# Sheet5.net
KiCad netlist of a schematic drawn in Altium Designer
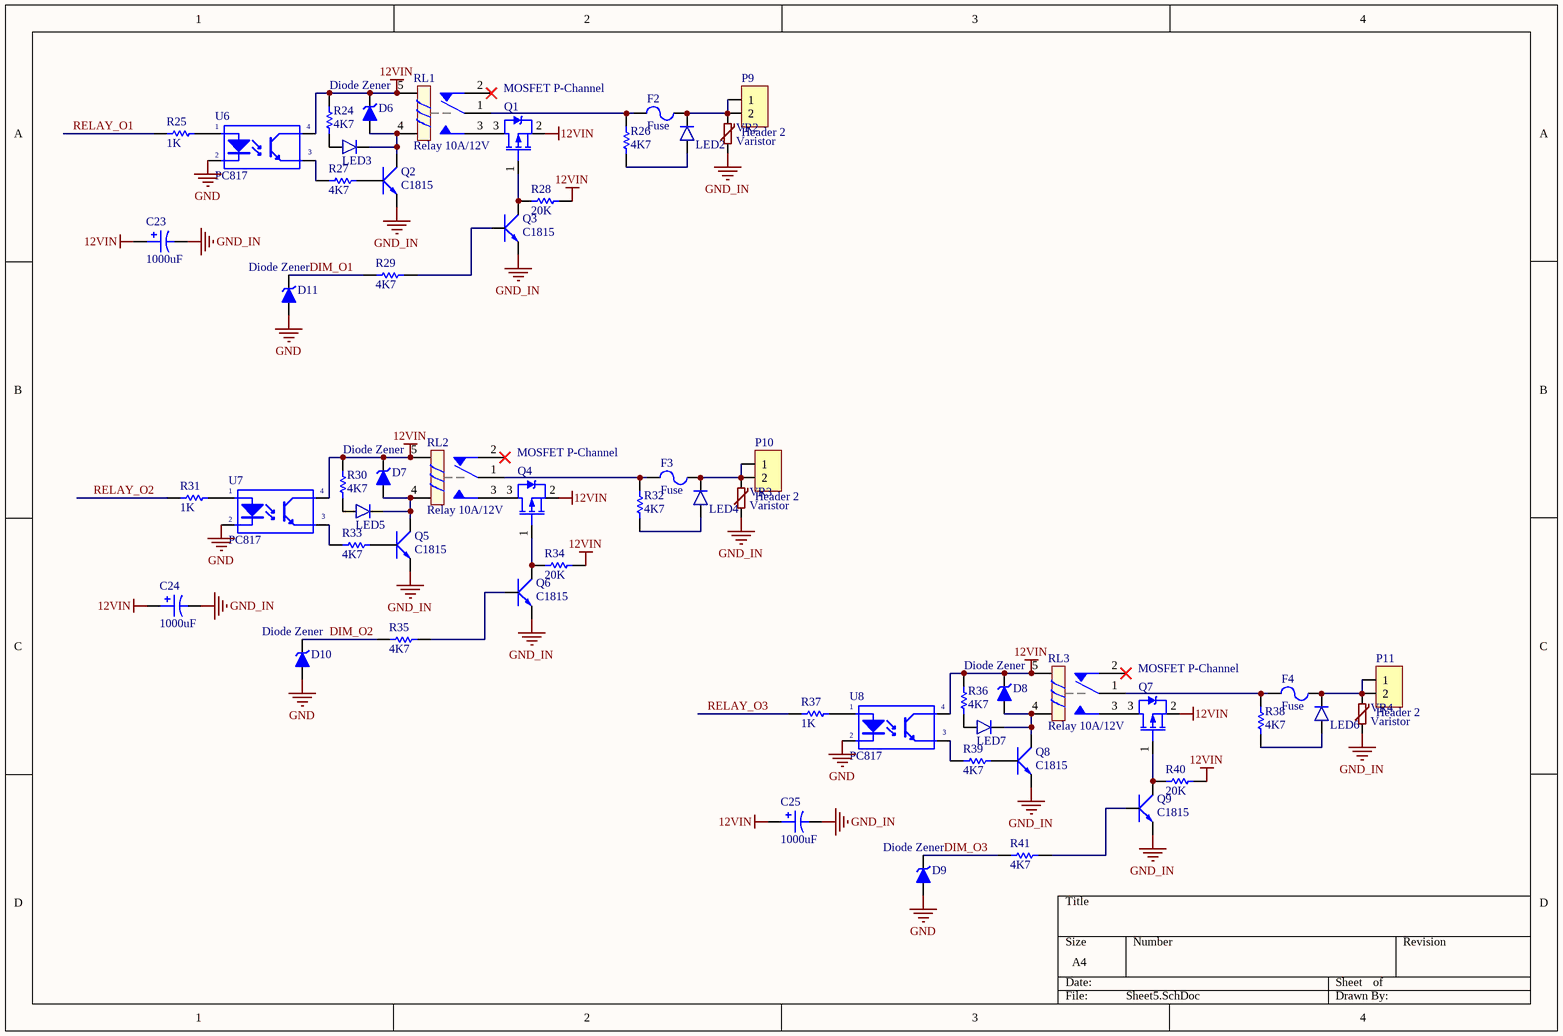
[diagram p0: Sheet5.SchDoc]

(export (version "E")
  (design (tool "Eeschema 10.0.6"))
  (components
    (comp (ref "C23")
      (value "1000uF")
      (footprint "RADIAL E")
      (description "Polarized Capacitor")
      (fields (field (name "Comment") "Cap Pol") (field (name "PUBLISHER") "Altium Limited"))
      (libsource (lib "phong") (part "Cap Pol"))
    )
    (comp (ref "C24")
      (value "1000uF")
      (footprint "RADIAL E")
      (description "Polarized Capacitor")
      (fields (field (name "Comment") "Cap Pol") (field (name "PUBLISHER") "Altium Limited"))
      (libsource (lib "phong") (part "Cap Pol"))
    )
    (comp (ref "C25")
      (value "1000uF")
      (footprint "RADIAL E")
      (description "Polarized Capacitor")
      (fields (field (name "Comment") "Cap Pol") (field (name "PUBLISHER") "Altium Limited"))
      (libsource (lib "phong") (part "Cap Pol"))
    )
    (comp (ref "D6")
      (value "Diode Zener")
      (footprint "SOD-80")
      (description "Zener Diode")
      (fields (field (name "PUBLISHER") "Altium Limited"))
      (libsource (lib "BKIT4U_LIB") (part "Diode Zener"))
    )
    (comp (ref "D7")
      (value "Diode Zener")
      (footprint "SOD-80")
      (description "Zener Diode")
      (fields (field (name "PUBLISHER") "Altium Limited"))
      (libsource (lib "BKIT4U_LIB") (part "Diode Zener"))
    )
    (comp (ref "D8")
      (value "Diode Zener")
      (footprint "SOD-80")
      (description "Zener Diode")
      (fields (field (name "PUBLISHER") "Altium Limited"))
      (libsource (lib "BKIT4U_LIB") (part "Diode Zener"))
    )
    (comp (ref "D9")
      (value "Diode Zener")
      (footprint "SOD-80")
      (description "Zener Diode")
      (fields (field (name "PUBLISHER") "Altium Limited"))
      (libsource (lib "BKIT4U_LIB") (part "Diode Zener"))
    )
    (comp (ref "D10")
      (value "Diode Zener")
      (footprint "SOD-80")
      (description "Zener Diode")
      (fields (field (name "PUBLISHER") "Altium Limited"))
      (libsource (lib "BKIT4U_LIB") (part "Diode Zener"))
    )
    (comp (ref "D11")
      (value "Diode Zener")
      (footprint "SOD-80")
      (description "Zener Diode")
      (fields (field (name "PUBLISHER") "Altium Limited"))
      (libsource (lib "BKIT4U_LIB") (part "Diode Zener"))
    )
    (comp (ref "F2")
      (value "Fuse")
      (footprint "DCAR Fuse holder")
      (libsource (lib "BKIT4U_LIB") (part "Fuse"))
    )
    (comp (ref "F3")
      (value "Fuse")
      (footprint "DCAR Fuse holder")
      (libsource (lib "BKIT4U_LIB") (part "Fuse"))
    )
    (comp (ref "F4")
      (value "Fuse")
      (footprint "DCAR Fuse holder")
      (libsource (lib "BKIT4U_LIB") (part "Fuse"))
    )
    (comp (ref "LED2")
      (value "Led")
      (footprint "Led SMD 0805")
      (description "Typical LED")
      (libsource (lib "BKIT4U_LIB") (part "Led"))
    )
    (comp (ref "LED3")
      (value "Led")
      (footprint "Led SMD 0805")
      (description "Typical LED")
      (libsource (lib "BKIT4U_LIB") (part "Led"))
    )
    (comp (ref "LED4")
      (value "Led")
      (footprint "Led SMD 0805")
      (description "Typical LED")
      (libsource (lib "BKIT4U_LIB") (part "Led"))
    )
    (comp (ref "LED5")
      (value "Led")
      (footprint "Led SMD 0805")
      (description "Typical LED")
      (libsource (lib "BKIT4U_LIB") (part "Led"))
    )
    (comp (ref "LED6")
      (value "Led")
      (footprint "Led SMD 0805")
      (description "Typical LED")
      (libsource (lib "BKIT4U_LIB") (part "Led"))
    )
    (comp (ref "LED7")
      (value "Led")
      (footprint "Led SMD 0805")
      (description "Typical LED")
      (libsource (lib "BKIT4U_LIB") (part "Led"))
    )
    (comp (ref "P9")
      (value "Header 2")
      (footprint "HDR Domino 2")
      (description "Header, 2-Pin")
      (fields (field (name "PUBLISHER") "Altium Limited"))
      (libsource (lib "BKIT4U_LIB") (part "Header 2"))
    )
    (comp (ref "P10")
      (value "Header 2")
      (footprint "HDR Domino 2")
      (description "Header, 2-Pin")
      (fields (field (name "PUBLISHER") "Altium Limited"))
      (libsource (lib "BKIT4U_LIB") (part "Header 2"))
    )
    (comp (ref "P11")
      (value "Header 2")
      (footprint "HDR Domino 2")
      (description "Header, 2-Pin")
      (fields (field (name "PUBLISHER") "Altium Limited"))
      (libsource (lib "BKIT4U_LIB") (part "Header 2"))
    )
    (comp (ref "Q1")
      (value "MOSFET P-Channel")
      (footprint "TO-252 (DPAK)")
      (libsource (lib "BKIT4U_LIB") (part "MOSFET P-Channel"))
    )
    (comp (ref "Q2")
      (value "C1815")
      (footprint "SOT23B")
      (description "NPN 600mW, ECB")
      (libsource (lib "syhaunguyen") (part "C1815"))
    )
    (comp (ref "Q3")
      (value "C1815")
      (footprint "SOT23B")
      (description "NPN 600mW, ECB")
      (libsource (lib "syhaunguyen") (part "C1815"))
    )
    (comp (ref "Q4")
      (value "MOSFET P-Channel")
      (footprint "TO-252 (DPAK)")
      (libsource (lib "BKIT4U_LIB") (part "MOSFET P-Channel"))
    )
    (comp (ref "Q5")
      (value "C1815")
      (footprint "SOT23B")
      (description "NPN 600mW, ECB")
      (libsource (lib "syhaunguyen") (part "C1815"))
    )
    (comp (ref "Q6")
      (value "C1815")
      (footprint "SOT23B")
      (description "NPN 600mW, ECB")
      (libsource (lib "syhaunguyen") (part "C1815"))
    )
    (comp (ref "Q7")
      (value "MOSFET P-Channel")
      (footprint "TO-252 (DPAK)")
      (libsource (lib "BKIT4U_LIB") (part "MOSFET P-Channel"))
    )
    (comp (ref "Q8")
      (value "C1815")
      (footprint "SOT23B")
      (description "NPN 600mW, ECB")
      (libsource (lib "syhaunguyen") (part "C1815"))
    )
    (comp (ref "Q9")
      (value "C1815")
      (footprint "SOT23B")
      (description "NPN 600mW, ECB")
      (libsource (lib "syhaunguyen") (part "C1815"))
    )
    (comp (ref "R24")
      (value "4K7")
      (footprint "R 0805 (2012)")
      (description "Resistor")
      (fields (field (name "PUBLISHER") "Altium Limited"))
      (libsource (lib "BKIT4U_LIB") (part "Resistor"))
    )
    (comp (ref "R25")
      (value "1K")
      (footprint "R 0805 (2012)")
      (description "Resistor")
      (fields (field (name "PUBLISHER") "Altium Limited"))
      (libsource (lib "BKIT4U_LIB") (part "Resistor"))
    )
    (comp (ref "R26")
      (value "4K7")
      (footprint "R 0805 (2012)")
      (description "Resistor")
      (fields (field (name "PUBLISHER") "Altium Limited"))
      (libsource (lib "BKIT4U_LIB") (part "Resistor"))
    )
    (comp (ref "R27")
      (value "4K7")
      (footprint "R 0805 (2012)")
      (description "Resistor")
      (fields (field (name "PUBLISHER") "Altium Limited"))
      (libsource (lib "BKIT4U_LIB") (part "Resistor"))
    )
    (comp (ref "R28")
      (value "20K")
      (footprint "R 0805 (2012)")
      (description "Resistor")
      (fields (field (name "PUBLISHER") "Altium Limited"))
      (libsource (lib "BKIT4U_LIB") (part "Resistor"))
    )
    (comp (ref "R29")
      (value "4K7")
      (footprint "R 0805 (2012)")
      (description "Resistor")
      (fields (field (name "PUBLISHER") "Altium Limited"))
      (libsource (lib "BKIT4U_LIB") (part "Resistor"))
    )
    (comp (ref "R30")
      (value "4K7")
      (footprint "R 0805 (2012)")
      (description "Resistor")
      (fields (field (name "PUBLISHER") "Altium Limited"))
      (libsource (lib "BKIT4U_LIB") (part "Resistor"))
    )
    (comp (ref "R31")
      (value "1K")
      (footprint "R 0805 (2012)")
      (description "Resistor")
      (fields (field (name "PUBLISHER") "Altium Limited"))
      (libsource (lib "BKIT4U_LIB") (part "Resistor"))
    )
    (comp (ref "R32")
      (value "4K7")
      (footprint "R 0805 (2012)")
      (description "Resistor")
      (fields (field (name "PUBLISHER") "Altium Limited"))
      (libsource (lib "BKIT4U_LIB") (part "Resistor"))
    )
    (comp (ref "R33")
      (value "4K7")
      (footprint "R 0805 (2012)")
      (description "Resistor")
      (fields (field (name "PUBLISHER") "Altium Limited"))
      (libsource (lib "BKIT4U_LIB") (part "Resistor"))
    )
    (comp (ref "R34")
      (value "20K")
      (footprint "R 0805 (2012)")
      (description "Resistor")
      (fields (field (name "PUBLISHER") "Altium Limited"))
      (libsource (lib "BKIT4U_LIB") (part "Resistor"))
    )
    (comp (ref "R35")
      (value "4K7")
      (footprint "R 0805 (2012)")
      (description "Resistor")
      (fields (field (name "PUBLISHER") "Altium Limited"))
      (libsource (lib "BKIT4U_LIB") (part "Resistor"))
    )
    (comp (ref "R36")
      (value "4K7")
      (footprint "R 0805 (2012)")
      (description "Resistor")
      (fields (field (name "PUBLISHER") "Altium Limited"))
      (libsource (lib "BKIT4U_LIB") (part "Resistor"))
    )
    (comp (ref "R37")
      (value "1K")
      (footprint "R 0805 (2012)")
      (description "Resistor")
      (fields (field (name "PUBLISHER") "Altium Limited"))
      (libsource (lib "BKIT4U_LIB") (part "Resistor"))
    )
    (comp (ref "R38")
      (value "4K7")
      (footprint "R 0805 (2012)")
      (description "Resistor")
      (fields (field (name "PUBLISHER") "Altium Limited"))
      (libsource (lib "BKIT4U_LIB") (part "Resistor"))
    )
    (comp (ref "R39")
      (value "4K7")
      (footprint "R 0805 (2012)")
      (description "Resistor")
      (fields (field (name "PUBLISHER") "Altium Limited"))
      (libsource (lib "BKIT4U_LIB") (part "Resistor"))
    )
    (comp (ref "R40")
      (value "20K")
      (footprint "R 0805 (2012)")
      (description "Resistor")
      (fields (field (name "PUBLISHER") "Altium Limited"))
      (libsource (lib "BKIT4U_LIB") (part "Resistor"))
    )
    (comp (ref "R41")
      (value "4K7")
      (footprint "R 0805 (2012)")
      (description "Resistor")
      (fields (field (name "PUBLISHER") "Altium Limited"))
      (libsource (lib "BKIT4U_LIB") (part "Resistor"))
    )
    (comp (ref "RL1")
      (value "Relay 10A/12V")
      (footprint "RL_SPDT_10A")
      (description "Relay SPDT,10A - 12VDC 5 Pin")
      (libsource (lib "BKIT4U_LIB") (part "Relay 1"))
    )
    (comp (ref "RL2")
      (value "Relay 10A/12V")
      (footprint "RL_SPDT_10A")
      (description "Relay SPDT,10A - 12VDC 5 Pin")
      (libsource (lib "BKIT4U_LIB") (part "Relay 1"))
    )
    (comp (ref "RL3")
      (value "Relay 10A/12V")
      (footprint "RL_SPDT_10A")
      (description "Relay SPDT,10A - 12VDC 5 Pin")
      (libsource (lib "BKIT4U_LIB") (part "Relay 1"))
    )
    (comp (ref "U6")
      (value "PC817")
      (footprint "SOP4 - PC817")
      (description "Single Opto")
      (libsource (lib "syhaunguyen") (part "PC817"))
    )
    (comp (ref "U7")
      (value "PC817")
      (footprint "SOP4 - PC817")
      (description "Single Opto")
      (libsource (lib "syhaunguyen") (part "PC817"))
    )
    (comp (ref "U8")
      (value "PC817")
      (footprint "SOP4 - PC817")
      (description "Single Opto")
      (libsource (lib "syhaunguyen") (part "PC817"))
    )
    (comp (ref "VR2")
      (value "Varistor")
      (footprint "VARISTOR DISC 5MM/7MM")
      (libsource (lib "chipfc_altium_libs") (part "Varistor"))
    )
    (comp (ref "VR3")
      (value "Varistor")
      (footprint "VARISTOR DISC 5MM/7MM")
      (libsource (lib "chipfc_altium_libs") (part "Varistor"))
    )
    (comp (ref "VR4")
      (value "Varistor")
      (footprint "VARISTOR DISC 5MM/7MM")
      (libsource (lib "chipfc_altium_libs") (part "Varistor"))
    )
  )
  (nets
    (net (code "1") (name "/DIM_O1") (class "Default")
      (node (ref "D11") (pin "2") (pinfunction "K_2") (pintype "passive"))
      (node (ref "R29") (pin "1") (pinfunction "1_1") (pintype "passive"))
    )
    (net (code "2") (name "/DIM_O2") (class "Default")
      (node (ref "D10") (pin "2") (pinfunction "K_2") (pintype "passive"))
      (node (ref "R35") (pin "1") (pinfunction "1_1") (pintype "passive"))
    )
    (net (code "3") (name "/DIM_O3") (class "Default")
      (node (ref "D9") (pin "2") (pinfunction "K_2") (pintype "passive"))
      (node (ref "R41") (pin "1") (pinfunction "1_1") (pintype "passive"))
    )
    (net (code "4") (name "/RELAY_O1") (class "Default")
      (node (ref "R25") (pin "2") (pinfunction "2_2") (pintype "passive"))
    )
    (net (code "5") (name "/RELAY_O2") (class "Default")
      (node (ref "R31") (pin "2") (pinfunction "2_2") (pintype "passive"))
    )
    (net (code "6") (name "/RELAY_O3") (class "Default")
      (node (ref "R37") (pin "2") (pinfunction "2_2") (pintype "passive"))
    )
    (net (code "7") (name "12VIN") (class "Default")
      (node (ref "C23") (pin "1") (pinfunction "1_1") (pintype "passive"))
      (node (ref "C24") (pin "1") (pinfunction "1_1") (pintype "passive"))
      (node (ref "C25") (pin "1") (pinfunction "1_1") (pintype "passive"))
      (node (ref "D6") (pin "2") (pinfunction "K_2") (pintype "passive"))
      (node (ref "D7") (pin "2") (pinfunction "K_2") (pintype "passive"))
      (node (ref "D8") (pin "2") (pinfunction "K_2") (pintype "passive"))
      (node (ref "Q1") (pin "2") (pinfunction "S_2") (pintype "passive"))
      (node (ref "Q4") (pin "2") (pinfunction "S_2") (pintype "passive"))
      (node (ref "Q7") (pin "2") (pinfunction "S_2") (pintype "passive"))
      (node (ref "R24") (pin "2") (pinfunction "2_2") (pintype "passive"))
      (node (ref "R28") (pin "2") (pinfunction "2_2") (pintype "passive"))
      (node (ref "R30") (pin "2") (pinfunction "2_2") (pintype "passive"))
      (node (ref "R34") (pin "2") (pinfunction "2_2") (pintype "passive"))
      (node (ref "R36") (pin "2") (pinfunction "2_2") (pintype "passive"))
      (node (ref "R40") (pin "2") (pinfunction "2_2") (pintype "passive"))
      (node (ref "RL1") (pin "5") (pinfunction "5_5") (pintype "passive"))
      (node (ref "RL2") (pin "5") (pinfunction "5_5") (pintype "passive"))
      (node (ref "RL3") (pin "5") (pinfunction "5_5") (pintype "passive"))
      (node (ref "U6") (pin "4") (pinfunction "C_4") (pintype "passive"))
      (node (ref "U7") (pin "4") (pinfunction "C_4") (pintype "passive"))
      (node (ref "U8") (pin "4") (pinfunction "C_4") (pintype "passive"))
    )
    (net (code "8") (name "GND") (class "Default")
      (node (ref "D10") (pin "1") (pinfunction "A_1") (pintype "passive"))
      (node (ref "D11") (pin "1") (pinfunction "A_1") (pintype "passive"))
      (node (ref "D9") (pin "1") (pinfunction "A_1") (pintype "passive"))
      (node (ref "U6") (pin "2") (pinfunction "K_2") (pintype "passive"))
      (node (ref "U7") (pin "2") (pinfunction "K_2") (pintype "passive"))
      (node (ref "U8") (pin "2") (pinfunction "K_2") (pintype "passive"))
    )
    (net (code "9") (name "GND_IN") (class "Default")
      (node (ref "C23") (pin "2") (pinfunction "2_2") (pintype "passive"))
      (node (ref "C24") (pin "2") (pinfunction "2_2") (pintype "passive"))
      (node (ref "C25") (pin "2") (pinfunction "2_2") (pintype "passive"))
      (node (ref "Q2") (pin "1") (pinfunction "E_1") (pintype "passive"))
      (node (ref "Q3") (pin "1") (pinfunction "E_1") (pintype "passive"))
      (node (ref "Q5") (pin "1") (pinfunction "E_1") (pintype "passive"))
      (node (ref "Q6") (pin "1") (pinfunction "E_1") (pintype "passive"))
      (node (ref "Q8") (pin "1") (pinfunction "E_1") (pintype "passive"))
      (node (ref "Q9") (pin "1") (pinfunction "E_1") (pintype "passive"))
      (node (ref "VR2") (pin "1") (pinfunction "1_1") (pintype "passive"))
      (node (ref "VR3") (pin "1") (pinfunction "1_1") (pintype "passive"))
      (node (ref "VR4") (pin "1") (pinfunction "1_1") (pintype "passive"))
    )
    (net (code "10") (name "Net-(D6-A)") (class "Default")
      (node (ref "D6") (pin "1") (pinfunction "A_1") (pintype "passive"))
      (node (ref "LED3") (pin "2") (pinfunction "K_2") (pintype "passive"))
      (node (ref "Q2") (pin "2") (pinfunction "C_2") (pintype "passive"))
      (node (ref "RL1") (pin "4") (pinfunction "4_4") (pintype "passive"))
    )
    (net (code "11") (name "Net-(D7-A)") (class "Default")
      (node (ref "D7") (pin "1") (pinfunction "A_1") (pintype "passive"))
      (node (ref "LED5") (pin "2") (pinfunction "K_2") (pintype "passive"))
      (node (ref "Q5") (pin "2") (pinfunction "C_2") (pintype "passive"))
      (node (ref "RL2") (pin "4") (pinfunction "4_4") (pintype "passive"))
    )
    (net (code "12") (name "Net-(D8-A)") (class "Default")
      (node (ref "D8") (pin "1") (pinfunction "A_1") (pintype "passive"))
      (node (ref "LED7") (pin "2") (pinfunction "K_2") (pintype "passive"))
      (node (ref "Q8") (pin "2") (pinfunction "C_2") (pintype "passive"))
      (node (ref "RL3") (pin "4") (pinfunction "4_4") (pintype "passive"))
    )
    (net (code "13") (name "Net-(F2-Pad1)") (class "Default")
      (node (ref "F2") (pin "1") (pinfunction "1_1") (pintype "passive"))
      (node (ref "R26") (pin "2") (pinfunction "2_2") (pintype "passive"))
      (node (ref "RL1") (pin "1") (pinfunction "1_1") (pintype "passive"))
    )
    (net (code "14") (name "Net-(F3-Pad1)") (class "Default")
      (node (ref "F3") (pin "1") (pinfunction "1_1") (pintype "passive"))
      (node (ref "R32") (pin "2") (pinfunction "2_2") (pintype "passive"))
      (node (ref "RL2") (pin "1") (pinfunction "1_1") (pintype "passive"))
    )
    (net (code "15") (name "Net-(F4-Pad1)") (class "Default")
      (node (ref "F4") (pin "1") (pinfunction "1_1") (pintype "passive"))
      (node (ref "R38") (pin "2") (pinfunction "2_2") (pintype "passive"))
      (node (ref "RL3") (pin "1") (pinfunction "1_1") (pintype "passive"))
    )
    (net (code "16") (name "Net-(LED2-A)") (class "Default")
      (node (ref "LED2") (pin "1") (pinfunction "A_1") (pintype "passive"))
      (node (ref "R26") (pin "1") (pinfunction "1_1") (pintype "passive"))
    )
    (net (code "17") (name "Net-(LED2-K)") (class "Default")
      (node (ref "F2") (pin "2") (pinfunction "2_2") (pintype "passive"))
      (node (ref "LED2") (pin "2") (pinfunction "K_2") (pintype "passive"))
      (node (ref "P9") (pin "1") (pinfunction "1_1") (pintype "passive"))
      (node (ref "P9") (pin "2") (pinfunction "2_2") (pintype "passive"))
      (node (ref "VR2") (pin "2") (pinfunction "2_2") (pintype "passive"))
    )
    (net (code "18") (name "Net-(LED3-A)") (class "Default")
      (node (ref "LED3") (pin "1") (pinfunction "A_1") (pintype "passive"))
      (node (ref "R24") (pin "1") (pinfunction "1_1") (pintype "passive"))
    )
    (net (code "19") (name "Net-(LED4-A)") (class "Default")
      (node (ref "LED4") (pin "1") (pinfunction "A_1") (pintype "passive"))
      (node (ref "R32") (pin "1") (pinfunction "1_1") (pintype "passive"))
    )
    (net (code "20") (name "Net-(LED4-K)") (class "Default")
      (node (ref "F3") (pin "2") (pinfunction "2_2") (pintype "passive"))
      (node (ref "LED4") (pin "2") (pinfunction "K_2") (pintype "passive"))
      (node (ref "P10") (pin "1") (pinfunction "1_1") (pintype "passive"))
      (node (ref "P10") (pin "2") (pinfunction "2_2") (pintype "passive"))
      (node (ref "VR3") (pin "2") (pinfunction "2_2") (pintype "passive"))
    )
    (net (code "21") (name "Net-(LED5-A)") (class "Default")
      (node (ref "LED5") (pin "1") (pinfunction "A_1") (pintype "passive"))
      (node (ref "R30") (pin "1") (pinfunction "1_1") (pintype "passive"))
    )
    (net (code "22") (name "Net-(LED6-A)") (class "Default")
      (node (ref "LED6") (pin "1") (pinfunction "A_1") (pintype "passive"))
      (node (ref "R38") (pin "1") (pinfunction "1_1") (pintype "passive"))
    )
    (net (code "23") (name "Net-(LED6-K)") (class "Default")
      (node (ref "F4") (pin "2") (pinfunction "2_2") (pintype "passive"))
      (node (ref "LED6") (pin "2") (pinfunction "K_2") (pintype "passive"))
      (node (ref "P11") (pin "1") (pinfunction "1_1") (pintype "passive"))
      (node (ref "P11") (pin "2") (pinfunction "2_2") (pintype "passive"))
      (node (ref "VR4") (pin "2") (pinfunction "2_2") (pintype "passive"))
    )
    (net (code "24") (name "Net-(LED7-A)") (class "Default")
      (node (ref "LED7") (pin "1") (pinfunction "A_1") (pintype "passive"))
      (node (ref "R36") (pin "1") (pinfunction "1_1") (pintype "passive"))
    )
    (net (code "25") (name "Net-(Q1-D)") (class "Default")
      (node (ref "Q1") (pin "3") (pinfunction "D_3") (pintype "passive"))
      (node (ref "RL1") (pin "3") (pinfunction "3_3") (pintype "passive"))
    )
    (net (code "26") (name "Net-(Q1-G)") (class "Default")
      (node (ref "Q1") (pin "1") (pinfunction "G_1") (pintype "passive"))
      (node (ref "Q3") (pin "2") (pinfunction "C_2") (pintype "passive"))
      (node (ref "R28") (pin "1") (pinfunction "1_1") (pintype "passive"))
    )
    (net (code "27") (name "Net-(Q2-B)") (class "Default")
      (node (ref "Q2") (pin "3") (pinfunction "B_3") (pintype "passive"))
      (node (ref "R27") (pin "2") (pinfunction "2_2") (pintype "passive"))
    )
    (net (code "28") (name "Net-(Q3-B)") (class "Default")
      (node (ref "Q3") (pin "3") (pinfunction "B_3") (pintype "passive"))
      (node (ref "R29") (pin "2") (pinfunction "2_2") (pintype "passive"))
    )
    (net (code "29") (name "Net-(Q4-D)") (class "Default")
      (node (ref "Q4") (pin "3") (pinfunction "D_3") (pintype "passive"))
      (node (ref "RL2") (pin "3") (pinfunction "3_3") (pintype "passive"))
    )
    (net (code "30") (name "Net-(Q4-G)") (class "Default")
      (node (ref "Q4") (pin "1") (pinfunction "G_1") (pintype "passive"))
      (node (ref "Q6") (pin "2") (pinfunction "C_2") (pintype "passive"))
      (node (ref "R34") (pin "1") (pinfunction "1_1") (pintype "passive"))
    )
    (net (code "31") (name "Net-(Q5-B)") (class "Default")
      (node (ref "Q5") (pin "3") (pinfunction "B_3") (pintype "passive"))
      (node (ref "R33") (pin "2") (pinfunction "2_2") (pintype "passive"))
    )
    (net (code "32") (name "Net-(Q6-B)") (class "Default")
      (node (ref "Q6") (pin "3") (pinfunction "B_3") (pintype "passive"))
      (node (ref "R35") (pin "2") (pinfunction "2_2") (pintype "passive"))
    )
    (net (code "33") (name "Net-(Q7-D)") (class "Default")
      (node (ref "Q7") (pin "3") (pinfunction "D_3") (pintype "passive"))
      (node (ref "RL3") (pin "3") (pinfunction "3_3") (pintype "passive"))
    )
    (net (code "34") (name "Net-(Q7-G)") (class "Default")
      (node (ref "Q7") (pin "1") (pinfunction "G_1") (pintype "passive"))
      (node (ref "Q9") (pin "2") (pinfunction "C_2") (pintype "passive"))
      (node (ref "R40") (pin "1") (pinfunction "1_1") (pintype "passive"))
    )
    (net (code "35") (name "Net-(Q8-B)") (class "Default")
      (node (ref "Q8") (pin "3") (pinfunction "B_3") (pintype "passive"))
      (node (ref "R39") (pin "2") (pinfunction "2_2") (pintype "passive"))
    )
    (net (code "36") (name "Net-(Q9-B)") (class "Default")
      (node (ref "Q9") (pin "3") (pinfunction "B_3") (pintype "passive"))
      (node (ref "R41") (pin "2") (pinfunction "2_2") (pintype "passive"))
    )
    (net (code "37") (name "Net-(U6-A)") (class "Default")
      (node (ref "R25") (pin "1") (pinfunction "1_1") (pintype "passive"))
      (node (ref "U6") (pin "1") (pinfunction "A_1") (pintype "passive"))
    )
    (net (code "38") (name "Net-(U6-E)") (class "Default")
      (node (ref "R27") (pin "1") (pinfunction "1_1") (pintype "passive"))
      (node (ref "U6") (pin "3") (pinfunction "E_3") (pintype "passive"))
    )
    (net (code "39") (name "Net-(U7-A)") (class "Default")
      (node (ref "R31") (pin "1") (pinfunction "1_1") (pintype "passive"))
      (node (ref "U7") (pin "1") (pinfunction "A_1") (pintype "passive"))
    )
    (net (code "40") (name "Net-(U7-E)") (class "Default")
      (node (ref "R33") (pin "1") (pinfunction "1_1") (pintype "passive"))
      (node (ref "U7") (pin "3") (pinfunction "E_3") (pintype "passive"))
    )
    (net (code "41") (name "Net-(U8-A)") (class "Default")
      (node (ref "R37") (pin "1") (pinfunction "1_1") (pintype "passive"))
      (node (ref "U8") (pin "1") (pinfunction "A_1") (pintype "passive"))
    )
    (net (code "42") (name "Net-(U8-E)") (class "Default")
      (node (ref "R39") (pin "1") (pinfunction "1_1") (pintype "passive"))
      (node (ref "U8") (pin "3") (pinfunction "E_3") (pintype "passive"))
    )
    (net (code "43") (name "unconnected-(RL1-Pad2)") (class "Default")
      (node (ref "RL1") (pin "2") (pinfunction "2_2") (pintype "passive+no_connect"))
    )
    (net (code "44") (name "unconnected-(RL2-Pad2)") (class "Default")
      (node (ref "RL2") (pin "2") (pinfunction "2_2") (pintype "passive+no_connect"))
    )
    (net (code "45") (name "unconnected-(RL3-Pad2)") (class "Default")
      (node (ref "RL3") (pin "2") (pinfunction "2_2") (pintype "passive+no_connect"))
    )
  )
)
